# uino-motor.net
KiCad netlist of a schematic drawn in EAGLE
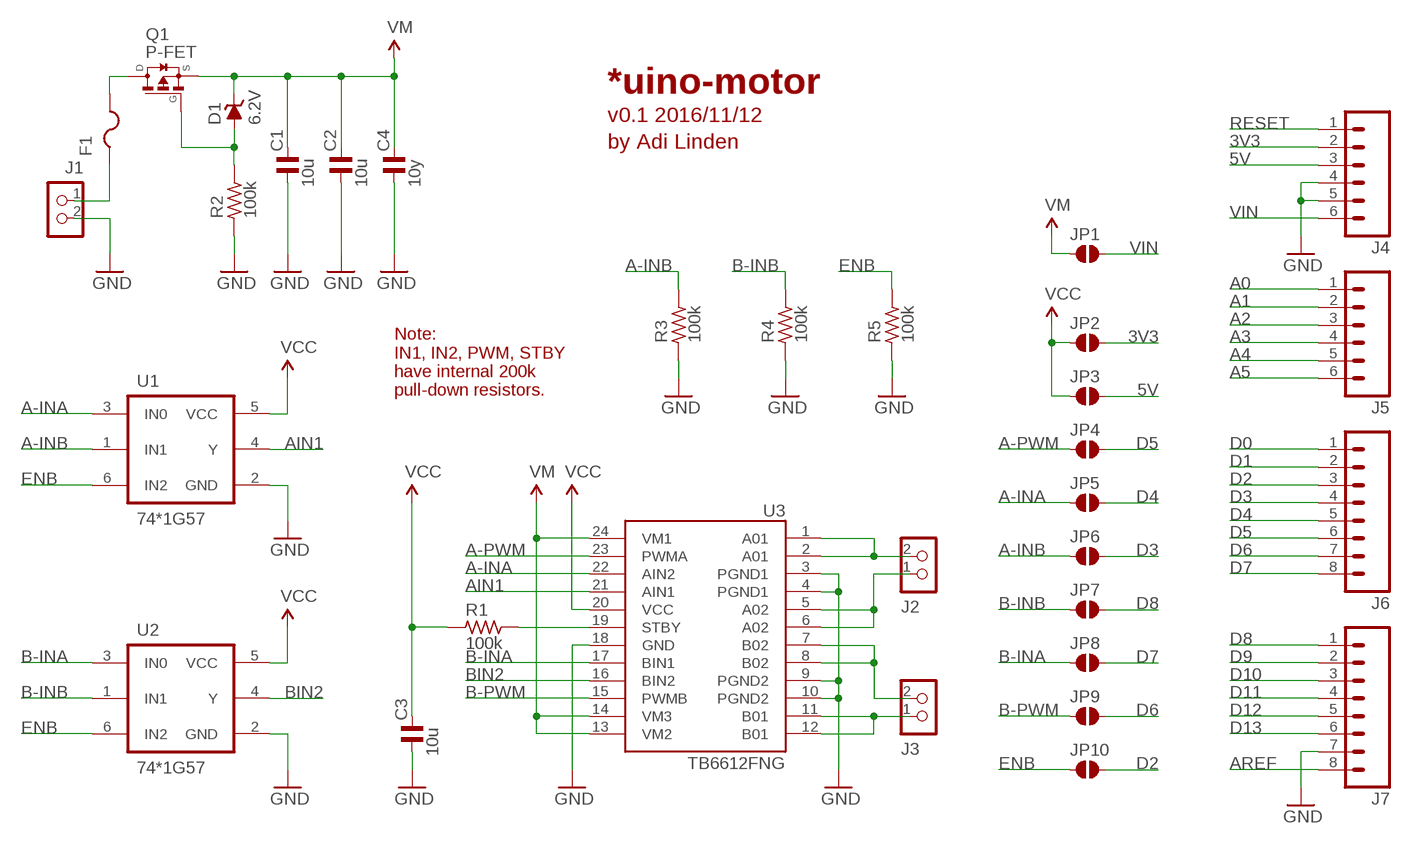
[diagram p0: schematic, sheet 1]

(export (version "E")
  (design (tool "Eeschema 10.0.6"))
  (components
    (comp (ref "C1")
      (value "10u")
      (footprint "eagle-import:C0805MP")
      (libsource (lib "eagle-import") (part "C_0805MP"))
    )
    (comp (ref "C2")
      (value "10u")
      (footprint "eagle-import:C0805MP")
      (libsource (lib "eagle-import") (part "C_0805MP"))
    )
    (comp (ref "C3")
      (value "10u")
      (footprint "eagle-import:C0805MP")
      (libsource (lib "eagle-import") (part "C_0805MP"))
    )
    (comp (ref "C4")
      (value "10y")
      (footprint "eagle-import:C0805MP")
      (libsource (lib "eagle-import") (part "C_0805MP"))
    )
    (comp (ref "D1")
      (value "6.2V")
      (footprint "eagle-import:SOD323")
      (libsource (lib "eagle-import") (part "BZX384"))
    )
    (comp (ref "F1")
      (value "FUSE_PTC-TH")
      (footprint "eagle-import:PTC")
      (libsource (lib "eagle-import") (part "FUSE_PTC-TH"))
    )
    (comp (ref "J1")
      (value "CON_TERMINAL_BLOCK_02-5MM")
      (footprint "eagle-import:TERMINAL_BLOCK_2P_5")
      (libsource (lib "eagle-import") (part "CON_TERMINAL_BLOCK_02-5MM"))
    )
    (comp (ref "J2")
      (value "CON_TERMINAL_BLOCK_02-5MM")
      (footprint "eagle-import:TERMINAL_BLOCK_2P_5")
      (libsource (lib "eagle-import") (part "CON_TERMINAL_BLOCK_02-5MM"))
    )
    (comp (ref "J3")
      (value "CON_TERMINAL_BLOCK_02-5MM")
      (footprint "eagle-import:TERMINAL_BLOCK_2P_5")
      (libsource (lib "eagle-import") (part "CON_TERMINAL_BLOCK_02-5MM"))
    )
    (comp (ref "J4")
      (value "M06SIP")
      (footprint "eagle-import:1X06")
      (libsource (lib "eagle-import") (part "M06SIP"))
    )
    (comp (ref "J5")
      (value "M06SIP")
      (footprint "eagle-import:1X06")
      (libsource (lib "eagle-import") (part "M06SIP"))
    )
    (comp (ref "J6")
      (value "M081X08")
      (footprint "eagle-import:1X08")
      (libsource (lib "eagle-import") (part "M081X08"))
    )
    (comp (ref "J7")
      (value "M081X08")
      (footprint "eagle-import:1X08")
      (libsource (lib "eagle-import") (part "M081X08"))
    )
    (comp (ref "JP1")
      (value "SJ-035")
      (footprint "eagle-import:SJ-035")
      (libsource (lib "eagle-import") (part "SJ-035"))
    )
    (comp (ref "JP2")
      (value "SJ-035")
      (footprint "eagle-import:SJ-035")
      (libsource (lib "eagle-import") (part "SJ-035"))
    )
    (comp (ref "JP3")
      (value "SJ-035")
      (footprint "eagle-import:SJ-035")
      (libsource (lib "eagle-import") (part "SJ-035"))
    )
    (comp (ref "JP4")
      (value "SJ-035")
      (footprint "eagle-import:SJ-035")
      (libsource (lib "eagle-import") (part "SJ-035"))
    )
    (comp (ref "JP5")
      (value "SJ-035")
      (footprint "eagle-import:SJ-035")
      (libsource (lib "eagle-import") (part "SJ-035"))
    )
    (comp (ref "JP6")
      (value "SJ-035")
      (footprint "eagle-import:SJ-035")
      (libsource (lib "eagle-import") (part "SJ-035"))
    )
    (comp (ref "JP7")
      (value "SJ-035")
      (footprint "eagle-import:SJ-035")
      (libsource (lib "eagle-import") (part "SJ-035"))
    )
    (comp (ref "JP8")
      (value "SJ-035")
      (footprint "eagle-import:SJ-035")
      (libsource (lib "eagle-import") (part "SJ-035"))
    )
    (comp (ref "JP9")
      (value "SJ-035")
      (footprint "eagle-import:SJ-035")
      (libsource (lib "eagle-import") (part "SJ-035"))
    )
    (comp (ref "JP10")
      (value "SJ-035")
      (footprint "eagle-import:SJ-035")
      (libsource (lib "eagle-import") (part "SJ-035"))
    )
    (comp (ref "Q1")
      (value "P-FET")
      (footprint "eagle-import:SOT23")
      (libsource (lib "eagle-import") (part "SI2307CDS"))
    )
    (comp (ref "R1")
      (value "100k")
      (footprint "eagle-import:R0805MP")
      (libsource (lib "eagle-import") (part "R_0805MP"))
    )
    (comp (ref "R2")
      (value "100k")
      (footprint "eagle-import:R0805MP")
      (libsource (lib "eagle-import") (part "R_0805MP"))
    )
    (comp (ref "R3")
      (value "100k")
      (footprint "eagle-import:R0805MP")
      (libsource (lib "eagle-import") (part "R_0805MP"))
    )
    (comp (ref "R4")
      (value "100k")
      (footprint "eagle-import:R0805MP")
      (libsource (lib "eagle-import") (part "R_0805MP"))
    )
    (comp (ref "R5")
      (value "100k")
      (footprint "eagle-import:R0805MP")
      (libsource (lib "eagle-import") (part "R_0805MP"))
    )
    (comp (ref "U1")
      (value "74*1G57")
      (footprint "eagle-import:SOT23-6")
      (libsource (lib "eagle-import") (part "SN74LVC1G97DBV"))
    )
    (comp (ref "U2")
      (value "74*1G57")
      (footprint "eagle-import:SOT23-6")
      (libsource (lib "eagle-import") (part "SN74LVC1G97DBV"))
    )
    (comp (ref "U3")
      (value "TB6612FNG")
      (footprint "eagle-import:SSOP24")
      (libsource (lib "eagle-import") (part "TB6612FNG"))
    )
  )
  (nets
    (net (code "1") (name "/3V3") (class "Default")
      (node (ref "J4") (pin "2") (pinfunction "2_2") (pintype "passive"))
      (node (ref "JP2") (pin "2") (pinfunction "2_2") (pintype "passive"))
    )
    (net (code "2") (name "/5V") (class "Default")
      (node (ref "J4") (pin "3") (pinfunction "3_3") (pintype "passive"))
      (node (ref "JP3") (pin "2") (pinfunction "2_2") (pintype "passive"))
    )
    (net (code "3") (name "/A-INA") (class "Default")
      (node (ref "JP5") (pin "1") (pinfunction "1_1") (pintype "passive"))
      (node (ref "U1") (pin "3") (pinfunction "IN0_3") (pintype "input"))
      (node (ref "U3") (pin "22") (pinfunction "AIN2_22") (pintype "bidirectional"))
    )
    (net (code "4") (name "/A-INB") (class "Default")
      (node (ref "JP6") (pin "1") (pinfunction "1_1") (pintype "passive"))
      (node (ref "R3") (pin "2") (pinfunction "2_2") (pintype "passive"))
      (node (ref "U1") (pin "1") (pinfunction "IN1_1") (pintype "input"))
    )
    (net (code "5") (name "/A-PWM") (class "Default")
      (node (ref "JP4") (pin "1") (pinfunction "1_1") (pintype "passive"))
      (node (ref "U3") (pin "23") (pinfunction "PWMA_23") (pintype "bidirectional"))
    )
    (net (code "6") (name "/A0") (class "Default")
      (node (ref "J5") (pin "1") (pinfunction "1_1") (pintype "passive"))
    )
    (net (code "7") (name "/A1") (class "Default")
      (node (ref "J5") (pin "2") (pinfunction "2_2") (pintype "passive"))
    )
    (net (code "8") (name "/A2") (class "Default")
      (node (ref "J5") (pin "3") (pinfunction "3_3") (pintype "passive"))
    )
    (net (code "9") (name "/A3") (class "Default")
      (node (ref "J5") (pin "4") (pinfunction "4_4") (pintype "passive"))
    )
    (net (code "10") (name "/A4") (class "Default")
      (node (ref "J5") (pin "5") (pinfunction "5_5") (pintype "passive"))
    )
    (net (code "11") (name "/A5") (class "Default")
      (node (ref "J5") (pin "6") (pinfunction "6_6") (pintype "passive"))
    )
    (net (code "12") (name "/AIN1") (class "Default")
      (node (ref "U1") (pin "4") (pinfunction "Y_4") (pintype "output"))
      (node (ref "U3") (pin "21") (pinfunction "AIN1_21") (pintype "bidirectional"))
    )
    (net (code "13") (name "/AREF") (class "Default")
      (node (ref "J7") (pin "8") (pinfunction "8_8") (pintype "passive"))
    )
    (net (code "14") (name "/B-INA") (class "Default")
      (node (ref "JP8") (pin "1") (pinfunction "1_1") (pintype "passive"))
      (node (ref "U2") (pin "3") (pinfunction "IN0_3") (pintype "input"))
      (node (ref "U3") (pin "17") (pinfunction "BIN1_17") (pintype "bidirectional"))
    )
    (net (code "15") (name "/B-INB") (class "Default")
      (node (ref "JP7") (pin "1") (pinfunction "1_1") (pintype "passive"))
      (node (ref "R4") (pin "2") (pinfunction "2_2") (pintype "passive"))
      (node (ref "U2") (pin "1") (pinfunction "IN1_1") (pintype "input"))
    )
    (net (code "16") (name "/B-PWM") (class "Default")
      (node (ref "JP9") (pin "1") (pinfunction "1_1") (pintype "passive"))
      (node (ref "U3") (pin "15") (pinfunction "PWMB_15") (pintype "bidirectional"))
    )
    (net (code "17") (name "/BIN2") (class "Default")
      (node (ref "U2") (pin "4") (pinfunction "Y_4") (pintype "output"))
      (node (ref "U3") (pin "16") (pinfunction "BIN2_16") (pintype "bidirectional"))
    )
    (net (code "18") (name "/D0") (class "Default")
      (node (ref "J6") (pin "1") (pinfunction "1_1") (pintype "passive"))
    )
    (net (code "19") (name "/D1") (class "Default")
      (node (ref "J6") (pin "2") (pinfunction "2_2") (pintype "passive"))
    )
    (net (code "20") (name "/D2") (class "Default")
      (node (ref "J6") (pin "3") (pinfunction "3_3") (pintype "passive"))
      (node (ref "JP10") (pin "2") (pinfunction "2_2") (pintype "passive"))
    )
    (net (code "21") (name "/D3") (class "Default")
      (node (ref "J6") (pin "4") (pinfunction "4_4") (pintype "passive"))
      (node (ref "JP6") (pin "2") (pinfunction "2_2") (pintype "passive"))
    )
    (net (code "22") (name "/D4") (class "Default")
      (node (ref "J6") (pin "5") (pinfunction "5_5") (pintype "passive"))
      (node (ref "JP5") (pin "2") (pinfunction "2_2") (pintype "passive"))
    )
    (net (code "23") (name "/D5") (class "Default")
      (node (ref "J6") (pin "6") (pinfunction "6_6") (pintype "passive"))
      (node (ref "JP4") (pin "2") (pinfunction "2_2") (pintype "passive"))
    )
    (net (code "24") (name "/D6") (class "Default")
      (node (ref "J6") (pin "7") (pinfunction "7_7") (pintype "passive"))
      (node (ref "JP9") (pin "2") (pinfunction "2_2") (pintype "passive"))
    )
    (net (code "25") (name "/D7") (class "Default")
      (node (ref "J6") (pin "8") (pinfunction "8_8") (pintype "passive"))
      (node (ref "JP8") (pin "2") (pinfunction "2_2") (pintype "passive"))
    )
    (net (code "26") (name "/D8") (class "Default")
      (node (ref "J7") (pin "1") (pinfunction "1_1") (pintype "passive"))
      (node (ref "JP7") (pin "2") (pinfunction "2_2") (pintype "passive"))
    )
    (net (code "27") (name "/D9") (class "Default")
      (node (ref "J7") (pin "2") (pinfunction "2_2") (pintype "passive"))
    )
    (net (code "28") (name "/D10") (class "Default")
      (node (ref "J7") (pin "3") (pinfunction "3_3") (pintype "passive"))
    )
    (net (code "29") (name "/D11") (class "Default")
      (node (ref "J7") (pin "4") (pinfunction "4_4") (pintype "passive"))
    )
    (net (code "30") (name "/D12") (class "Default")
      (node (ref "J7") (pin "5") (pinfunction "5_5") (pintype "passive"))
    )
    (net (code "31") (name "/D13") (class "Default")
      (node (ref "J7") (pin "6") (pinfunction "6_6") (pintype "passive"))
    )
    (net (code "32") (name "/ENB") (class "Default")
      (node (ref "JP10") (pin "1") (pinfunction "1_1") (pintype "passive"))
      (node (ref "R5") (pin "2") (pinfunction "2_2") (pintype "passive"))
      (node (ref "U1") (pin "6") (pinfunction "IN2_6") (pintype "input"))
      (node (ref "U2") (pin "6") (pinfunction "IN2_6") (pintype "input"))
    )
    (net (code "33") (name "/RESET") (class "Default")
      (node (ref "J4") (pin "1") (pinfunction "1_1") (pintype "passive"))
    )
    (net (code "34") (name "/VIN") (class "Default")
      (node (ref "J4") (pin "6") (pinfunction "6_6") (pintype "passive"))
      (node (ref "JP1") (pin "2") (pinfunction "2_2") (pintype "passive"))
    )
    (net (code "35") (name "GND") (class "Default")
      (node (ref "C1") (pin "1") (pinfunction "1_1") (pintype "passive"))
      (node (ref "C2") (pin "1") (pinfunction "1_1") (pintype "passive"))
      (node (ref "C3") (pin "1") (pinfunction "1_1") (pintype "passive"))
      (node (ref "C4") (pin "1") (pinfunction "1_1") (pintype "passive"))
      (node (ref "J1") (pin "2") (pinfunction "2_2") (pintype "passive"))
      (node (ref "J4") (pin "4") (pinfunction "4_4") (pintype "passive"))
      (node (ref "J4") (pin "5") (pinfunction "5_5") (pintype "passive"))
      (node (ref "J7") (pin "7") (pinfunction "7_7") (pintype "passive"))
      (node (ref "R2") (pin "1") (pinfunction "1_1") (pintype "passive"))
      (node (ref "R3") (pin "1") (pinfunction "1_1") (pintype "passive"))
      (node (ref "R4") (pin "1") (pinfunction "1_1") (pintype "passive"))
      (node (ref "R5") (pin "1") (pinfunction "1_1") (pintype "passive"))
      (node (ref "U1") (pin "2") (pinfunction "GND_2") (pintype "power_in"))
      (node (ref "U2") (pin "2") (pinfunction "GND_2") (pintype "power_in"))
      (node (ref "U3") (pin "10") (pinfunction "PGND2_10") (pintype "bidirectional"))
      (node (ref "U3") (pin "18") (pinfunction "GND_18") (pintype "bidirectional"))
      (node (ref "U3") (pin "3") (pinfunction "PGND1_3") (pintype "bidirectional"))
      (node (ref "U3") (pin "4") (pinfunction "PGND1_4") (pintype "bidirectional"))
      (node (ref "U3") (pin "9") (pinfunction "PGND2_9") (pintype "bidirectional"))
    )
    (net (code "36") (name "Net-(F1-1)") (class "Default")
      (node (ref "F1") (pin "P$1") (pinfunction "1_P$1") (pintype "passive"))
      (node (ref "J1") (pin "1") (pinfunction "1_1") (pintype "passive"))
    )
    (net (code "37") (name "Net-(F1-2)") (class "Default")
      (node (ref "F1") (pin "P$2") (pinfunction "2_P$2") (pintype "passive"))
      (node (ref "Q1") (pin "3") (pinfunction "D_3") (pintype "passive"))
    )
    (net (code "38") (name "Net-(J2-Pad1)") (class "Default")
      (node (ref "J2") (pin "1") (pinfunction "1_1") (pintype "passive"))
      (node (ref "U3") (pin "5") (pinfunction "A02_5") (pintype "bidirectional"))
      (node (ref "U3") (pin "6") (pinfunction "A02_6") (pintype "bidirectional"))
    )
    (net (code "39") (name "Net-(J2-Pad2)") (class "Default")
      (node (ref "J2") (pin "2") (pinfunction "2_2") (pintype "passive"))
      (node (ref "U3") (pin "1") (pinfunction "A01_1") (pintype "bidirectional"))
      (node (ref "U3") (pin "2") (pinfunction "A01_2") (pintype "bidirectional"))
    )
    (net (code "40") (name "Net-(J3-Pad1)") (class "Default")
      (node (ref "J3") (pin "1") (pinfunction "1_1") (pintype "passive"))
      (node (ref "U3") (pin "11") (pinfunction "B01_11") (pintype "bidirectional"))
      (node (ref "U3") (pin "12") (pinfunction "B01_12") (pintype "bidirectional"))
    )
    (net (code "41") (name "Net-(J3-Pad2)") (class "Default")
      (node (ref "J3") (pin "2") (pinfunction "2_2") (pintype "passive"))
      (node (ref "U3") (pin "7") (pinfunction "B02_7") (pintype "bidirectional"))
      (node (ref "U3") (pin "8") (pinfunction "B02_8") (pintype "bidirectional"))
    )
    (net (code "42") (name "Net-(Q1-G)") (class "Default")
      (node (ref "D1") (pin "A") (pinfunction "A_A") (pintype "passive"))
      (node (ref "Q1") (pin "1") (pinfunction "G_1") (pintype "passive"))
      (node (ref "R2") (pin "2") (pinfunction "2_2") (pintype "passive"))
    )
    (net (code "43") (name "Net-(U3-STBY)") (class "Default")
      (node (ref "R1") (pin "2") (pinfunction "2_2") (pintype "passive"))
      (node (ref "U3") (pin "19") (pinfunction "STBY_19") (pintype "bidirectional"))
    )
    (net (code "44") (name "VCC") (class "Default")
      (node (ref "C3") (pin "2") (pinfunction "2_2") (pintype "passive"))
      (node (ref "JP2") (pin "1") (pinfunction "1_1") (pintype "passive"))
      (node (ref "JP3") (pin "1") (pinfunction "1_1") (pintype "passive"))
      (node (ref "R1") (pin "1") (pinfunction "1_1") (pintype "passive"))
      (node (ref "U1") (pin "5") (pinfunction "VCC_5") (pintype "power_in"))
      (node (ref "U2") (pin "5") (pinfunction "VCC_5") (pintype "power_in"))
      (node (ref "U3") (pin "20") (pinfunction "VCC_20") (pintype "bidirectional"))
    )
    (net (code "45") (name "VM") (class "Default")
      (node (ref "C1") (pin "2") (pinfunction "2_2") (pintype "passive"))
      (node (ref "C2") (pin "2") (pinfunction "2_2") (pintype "passive"))
      (node (ref "C4") (pin "2") (pinfunction "2_2") (pintype "passive"))
      (node (ref "D1") (pin "C") (pinfunction "C_C") (pintype "passive"))
      (node (ref "JP1") (pin "1") (pinfunction "1_1") (pintype "passive"))
      (node (ref "Q1") (pin "2") (pinfunction "S_2") (pintype "passive"))
      (node (ref "U3") (pin "13") (pinfunction "VM2_13") (pintype "bidirectional"))
      (node (ref "U3") (pin "14") (pinfunction "VM3_14") (pintype "bidirectional"))
      (node (ref "U3") (pin "24") (pinfunction "VM1_24") (pintype "bidirectional"))
    )
  )
)
